# PCB-TLY-JACK-LEDPHOENIX.net
KiCad netlist of a schematic drawn in EAGLE
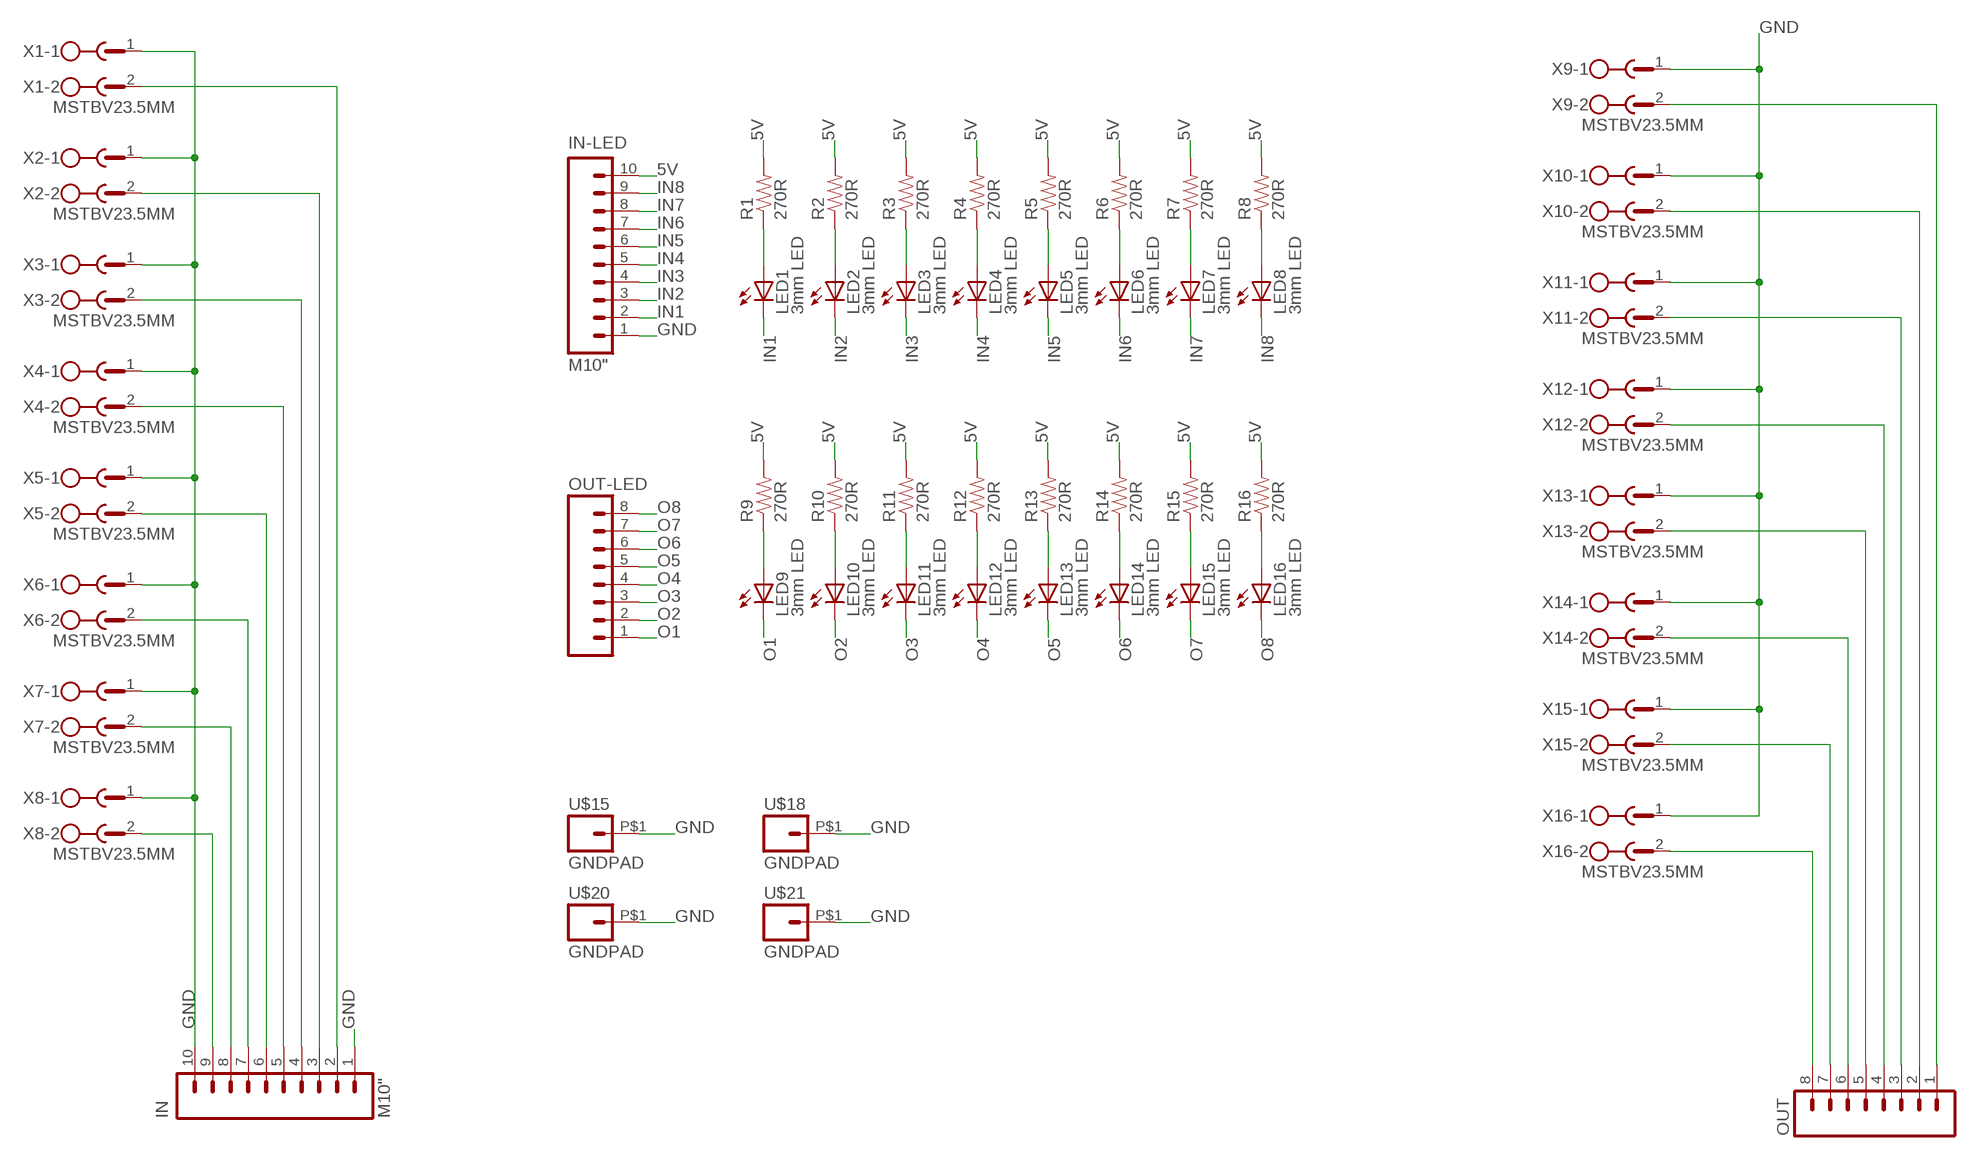
[diagram p0: schematic, sheet 1]

(export (version "E")
  (design (tool "Eeschema 10.0.6"))
  (components
    (comp (ref "IN")
      (value "M10\"")
      (footprint "eagle-import:1X10")
      (libsource (lib "eagle-import") (part "M10{dblquote}"))
    )
    (comp (ref "IN-LED")
      (value "M10\"")
      (footprint "eagle-import:1X10")
      (libsource (lib "eagle-import") (part "M10{dblquote}"))
    )
    (comp (ref "LED1")
      (value "3mm LED")
      (footprint "eagle-import:LED-1206")
      (libsource (lib "eagle-import") (part "LED1206"))
    )
    (comp (ref "LED2")
      (value "3mm LED")
      (footprint "eagle-import:LED-1206")
      (libsource (lib "eagle-import") (part "LED1206"))
    )
    (comp (ref "LED3")
      (value "3mm LED")
      (footprint "eagle-import:LED-1206")
      (libsource (lib "eagle-import") (part "LED1206"))
    )
    (comp (ref "LED4")
      (value "3mm LED")
      (footprint "eagle-import:LED-1206")
      (libsource (lib "eagle-import") (part "LED1206"))
    )
    (comp (ref "LED5")
      (value "3mm LED")
      (footprint "eagle-import:LED-1206")
      (libsource (lib "eagle-import") (part "LED1206"))
    )
    (comp (ref "LED6")
      (value "3mm LED")
      (footprint "eagle-import:LED-1206")
      (libsource (lib "eagle-import") (part "LED1206"))
    )
    (comp (ref "LED7")
      (value "3mm LED")
      (footprint "eagle-import:LED-1206")
      (libsource (lib "eagle-import") (part "LED1206"))
    )
    (comp (ref "LED8")
      (value "3mm LED")
      (footprint "eagle-import:LED-1206")
      (libsource (lib "eagle-import") (part "LED1206"))
    )
    (comp (ref "LED9")
      (value "3mm LED")
      (footprint "eagle-import:LED-1206")
      (libsource (lib "eagle-import") (part "LED1206"))
    )
    (comp (ref "LED10")
      (value "3mm LED")
      (footprint "eagle-import:LED-1206")
      (libsource (lib "eagle-import") (part "LED1206"))
    )
    (comp (ref "LED11")
      (value "3mm LED")
      (footprint "eagle-import:LED-1206")
      (libsource (lib "eagle-import") (part "LED1206"))
    )
    (comp (ref "LED12")
      (value "3mm LED")
      (footprint "eagle-import:LED-1206")
      (libsource (lib "eagle-import") (part "LED1206"))
    )
    (comp (ref "LED13")
      (value "3mm LED")
      (footprint "eagle-import:LED-1206")
      (libsource (lib "eagle-import") (part "LED1206"))
    )
    (comp (ref "LED14")
      (value "3mm LED")
      (footprint "eagle-import:LED-1206")
      (libsource (lib "eagle-import") (part "LED1206"))
    )
    (comp (ref "LED15")
      (value "3mm LED")
      (footprint "eagle-import:LED-1206")
      (libsource (lib "eagle-import") (part "LED1206"))
    )
    (comp (ref "LED16")
      (value "3mm LED")
      (footprint "eagle-import:LED-1206")
      (libsource (lib "eagle-import") (part "LED1206"))
    )
    (comp (ref "OUT")
      (value "M081X08")
      (footprint "eagle-import:1X08")
      (libsource (lib "eagle-import") (part "M081X08"))
    )
    (comp (ref "OUT-LED")
      (value "M081X08")
      (footprint "eagle-import:1X08")
      (libsource (lib "eagle-import") (part "M081X08"))
    )
    (comp (ref "R1")
      (value "270R")
      (footprint "eagle-import:0603-RES")
      (libsource (lib "eagle-import") (part "RESISTOR0603-RES"))
    )
    (comp (ref "R2")
      (value "270R")
      (footprint "eagle-import:0603-RES")
      (libsource (lib "eagle-import") (part "RESISTOR0603-RES"))
    )
    (comp (ref "R3")
      (value "270R")
      (footprint "eagle-import:0603-RES")
      (libsource (lib "eagle-import") (part "RESISTOR0603-RES"))
    )
    (comp (ref "R4")
      (value "270R")
      (footprint "eagle-import:0603-RES")
      (libsource (lib "eagle-import") (part "RESISTOR0603-RES"))
    )
    (comp (ref "R5")
      (value "270R")
      (footprint "eagle-import:0603-RES")
      (libsource (lib "eagle-import") (part "RESISTOR0603-RES"))
    )
    (comp (ref "R6")
      (value "270R")
      (footprint "eagle-import:0603-RES")
      (libsource (lib "eagle-import") (part "RESISTOR0603-RES"))
    )
    (comp (ref "R7")
      (value "270R")
      (footprint "eagle-import:0603-RES")
      (libsource (lib "eagle-import") (part "RESISTOR0603-RES"))
    )
    (comp (ref "R8")
      (value "270R")
      (footprint "eagle-import:0603-RES")
      (libsource (lib "eagle-import") (part "RESISTOR0603-RES"))
    )
    (comp (ref "R9")
      (value "270R")
      (footprint "eagle-import:0603-RES")
      (libsource (lib "eagle-import") (part "RESISTOR0603-RES"))
    )
    (comp (ref "R10")
      (value "270R")
      (footprint "eagle-import:0603-RES")
      (libsource (lib "eagle-import") (part "RESISTOR0603-RES"))
    )
    (comp (ref "R11")
      (value "270R")
      (footprint "eagle-import:0603-RES")
      (libsource (lib "eagle-import") (part "RESISTOR0603-RES"))
    )
    (comp (ref "R12")
      (value "270R")
      (footprint "eagle-import:0603-RES")
      (libsource (lib "eagle-import") (part "RESISTOR0603-RES"))
    )
    (comp (ref "R13")
      (value "270R")
      (footprint "eagle-import:0603-RES")
      (libsource (lib "eagle-import") (part "RESISTOR0603-RES"))
    )
    (comp (ref "R14")
      (value "270R")
      (footprint "eagle-import:0603-RES")
      (libsource (lib "eagle-import") (part "RESISTOR0603-RES"))
    )
    (comp (ref "R15")
      (value "270R")
      (footprint "eagle-import:0603-RES")
      (libsource (lib "eagle-import") (part "RESISTOR0603-RES"))
    )
    (comp (ref "R16")
      (value "270R")
      (footprint "eagle-import:0603-RES")
      (libsource (lib "eagle-import") (part "RESISTOR0603-RES"))
    )
    (comp (ref "U$15")
      (value "GNDPAD")
      (footprint "eagle-import:3.2MMPAD")
      (libsource (lib "eagle-import") (part "GNDPAD"))
    )
    (comp (ref "U$18")
      (value "GNDPAD")
      (footprint "eagle-import:3.2MMPAD")
      (libsource (lib "eagle-import") (part "GNDPAD"))
    )
    (comp (ref "U$20")
      (value "GNDPAD")
      (footprint "eagle-import:3.2MMPAD")
      (libsource (lib "eagle-import") (part "GNDPAD"))
    )
    (comp (ref "U$21")
      (value "GNDPAD")
      (footprint "eagle-import:3.2MMPAD")
      (libsource (lib "eagle-import") (part "GNDPAD"))
    )
    (comp (ref "X1")
      (value "MSTBV23.5MM")
      (footprint "eagle-import:MSTBV2-3.5")
      (libsource (lib "eagle-import") (part "MSTBV23.5MM"))
    )
    (comp (ref "X2")
      (value "MSTBV23.5MM")
      (footprint "eagle-import:MSTBV2-3.5")
      (libsource (lib "eagle-import") (part "MSTBV23.5MM"))
    )
    (comp (ref "X3")
      (value "MSTBV23.5MM")
      (footprint "eagle-import:MSTBV2-3.5")
      (libsource (lib "eagle-import") (part "MSTBV23.5MM"))
    )
    (comp (ref "X4")
      (value "MSTBV23.5MM")
      (footprint "eagle-import:MSTBV2-3.5")
      (libsource (lib "eagle-import") (part "MSTBV23.5MM"))
    )
    (comp (ref "X5")
      (value "MSTBV23.5MM")
      (footprint "eagle-import:MSTBV2-3.5")
      (libsource (lib "eagle-import") (part "MSTBV23.5MM"))
    )
    (comp (ref "X6")
      (value "MSTBV23.5MM")
      (footprint "eagle-import:MSTBV2-3.5")
      (libsource (lib "eagle-import") (part "MSTBV23.5MM"))
    )
    (comp (ref "X7")
      (value "MSTBV23.5MM")
      (footprint "eagle-import:MSTBV2-3.5")
      (libsource (lib "eagle-import") (part "MSTBV23.5MM"))
    )
    (comp (ref "X8")
      (value "MSTBV23.5MM")
      (footprint "eagle-import:MSTBV2-3.5")
      (libsource (lib "eagle-import") (part "MSTBV23.5MM"))
    )
    (comp (ref "X9")
      (value "MSTBV23.5MM")
      (footprint "eagle-import:MSTBV2-3.5")
      (libsource (lib "eagle-import") (part "MSTBV23.5MM"))
    )
    (comp (ref "X10")
      (value "MSTBV23.5MM")
      (footprint "eagle-import:MSTBV2-3.5")
      (libsource (lib "eagle-import") (part "MSTBV23.5MM"))
    )
    (comp (ref "X11")
      (value "MSTBV23.5MM")
      (footprint "eagle-import:MSTBV2-3.5")
      (libsource (lib "eagle-import") (part "MSTBV23.5MM"))
    )
    (comp (ref "X12")
      (value "MSTBV23.5MM")
      (footprint "eagle-import:MSTBV2-3.5")
      (libsource (lib "eagle-import") (part "MSTBV23.5MM"))
    )
    (comp (ref "X13")
      (value "MSTBV23.5MM")
      (footprint "eagle-import:MSTBV2-3.5")
      (libsource (lib "eagle-import") (part "MSTBV23.5MM"))
    )
    (comp (ref "X14")
      (value "MSTBV23.5MM")
      (footprint "eagle-import:MSTBV2-3.5")
      (libsource (lib "eagle-import") (part "MSTBV23.5MM"))
    )
    (comp (ref "X15")
      (value "MSTBV23.5MM")
      (footprint "eagle-import:MSTBV2-3.5")
      (libsource (lib "eagle-import") (part "MSTBV23.5MM"))
    )
    (comp (ref "X16")
      (value "MSTBV23.5MM")
      (footprint "eagle-import:MSTBV2-3.5")
      (libsource (lib "eagle-import") (part "MSTBV23.5MM"))
    )
  )
  (nets
    (net (code "1") (name "/5V") (class "Default")
      (node (ref "IN-LED") (pin "10") (pinfunction "10_10") (pintype "passive"))
      (node (ref "R1") (pin "2") (pinfunction "2_2") (pintype "passive"))
      (node (ref "R10") (pin "2") (pinfunction "2_2") (pintype "passive"))
      (node (ref "R11") (pin "2") (pinfunction "2_2") (pintype "passive"))
      (node (ref "R12") (pin "2") (pinfunction "2_2") (pintype "passive"))
      (node (ref "R13") (pin "2") (pinfunction "2_2") (pintype "passive"))
      (node (ref "R14") (pin "2") (pinfunction "2_2") (pintype "passive"))
      (node (ref "R15") (pin "2") (pinfunction "2_2") (pintype "passive"))
      (node (ref "R16") (pin "2") (pinfunction "2_2") (pintype "passive"))
      (node (ref "R2") (pin "2") (pinfunction "2_2") (pintype "passive"))
      (node (ref "R3") (pin "2") (pinfunction "2_2") (pintype "passive"))
      (node (ref "R4") (pin "2") (pinfunction "2_2") (pintype "passive"))
      (node (ref "R5") (pin "2") (pinfunction "2_2") (pintype "passive"))
      (node (ref "R6") (pin "2") (pinfunction "2_2") (pintype "passive"))
      (node (ref "R7") (pin "2") (pinfunction "2_2") (pintype "passive"))
      (node (ref "R8") (pin "2") (pinfunction "2_2") (pintype "passive"))
      (node (ref "R9") (pin "2") (pinfunction "2_2") (pintype "passive"))
    )
    (net (code "2") (name "/GND") (class "Default")
      (node (ref "IN") (pin "1") (pinfunction "1_1") (pintype "passive"))
      (node (ref "IN") (pin "10") (pinfunction "10_10") (pintype "passive"))
      (node (ref "IN-LED") (pin "1") (pinfunction "1_1") (pintype "passive"))
      (node (ref "U$15") (pin "P$1") (pinfunction "1_P$1") (pintype "passive"))
      (node (ref "U$18") (pin "P$1") (pinfunction "1_P$1") (pintype "passive"))
      (node (ref "U$20") (pin "P$1") (pinfunction "1_P$1") (pintype "passive"))
      (node (ref "U$21") (pin "P$1") (pinfunction "1_P$1") (pintype "passive"))
      (node (ref "X1") (pin "1") (pinfunction "1_1") (pintype "passive"))
      (node (ref "X10") (pin "1") (pinfunction "1_1") (pintype "passive"))
      (node (ref "X11") (pin "1") (pinfunction "1_1") (pintype "passive"))
      (node (ref "X12") (pin "1") (pinfunction "1_1") (pintype "passive"))
      (node (ref "X13") (pin "1") (pinfunction "1_1") (pintype "passive"))
      (node (ref "X14") (pin "1") (pinfunction "1_1") (pintype "passive"))
      (node (ref "X15") (pin "1") (pinfunction "1_1") (pintype "passive"))
      (node (ref "X16") (pin "1") (pinfunction "1_1") (pintype "passive"))
      (node (ref "X2") (pin "1") (pinfunction "1_1") (pintype "passive"))
      (node (ref "X3") (pin "1") (pinfunction "1_1") (pintype "passive"))
      (node (ref "X4") (pin "1") (pinfunction "1_1") (pintype "passive"))
      (node (ref "X5") (pin "1") (pinfunction "1_1") (pintype "passive"))
      (node (ref "X6") (pin "1") (pinfunction "1_1") (pintype "passive"))
      (node (ref "X7") (pin "1") (pinfunction "1_1") (pintype "passive"))
      (node (ref "X8") (pin "1") (pinfunction "1_1") (pintype "passive"))
      (node (ref "X9") (pin "1") (pinfunction "1_1") (pintype "passive"))
    )
    (net (code "3") (name "/IN1") (class "Default")
      (node (ref "IN-LED") (pin "2") (pinfunction "2_2") (pintype "passive"))
      (node (ref "LED1") (pin "C") (pinfunction "C_C") (pintype "passive"))
    )
    (net (code "4") (name "/IN2") (class "Default")
      (node (ref "IN-LED") (pin "3") (pinfunction "3_3") (pintype "passive"))
      (node (ref "LED2") (pin "C") (pinfunction "C_C") (pintype "passive"))
    )
    (net (code "5") (name "/IN3") (class "Default")
      (node (ref "IN-LED") (pin "4") (pinfunction "4_4") (pintype "passive"))
      (node (ref "LED3") (pin "C") (pinfunction "C_C") (pintype "passive"))
    )
    (net (code "6") (name "/IN4") (class "Default")
      (node (ref "IN-LED") (pin "5") (pinfunction "5_5") (pintype "passive"))
      (node (ref "LED4") (pin "C") (pinfunction "C_C") (pintype "passive"))
    )
    (net (code "7") (name "/IN5") (class "Default")
      (node (ref "IN-LED") (pin "6") (pinfunction "6_6") (pintype "passive"))
      (node (ref "LED5") (pin "C") (pinfunction "C_C") (pintype "passive"))
    )
    (net (code "8") (name "/IN6") (class "Default")
      (node (ref "IN-LED") (pin "7") (pinfunction "7_7") (pintype "passive"))
      (node (ref "LED6") (pin "C") (pinfunction "C_C") (pintype "passive"))
    )
    (net (code "9") (name "/IN7") (class "Default")
      (node (ref "IN-LED") (pin "8") (pinfunction "8_8") (pintype "passive"))
      (node (ref "LED7") (pin "C") (pinfunction "C_C") (pintype "passive"))
    )
    (net (code "10") (name "/IN8") (class "Default")
      (node (ref "IN-LED") (pin "9") (pinfunction "9_9") (pintype "passive"))
      (node (ref "LED8") (pin "C") (pinfunction "C_C") (pintype "passive"))
    )
    (net (code "11") (name "/O1") (class "Default")
      (node (ref "LED9") (pin "C") (pinfunction "C_C") (pintype "passive"))
      (node (ref "OUT-LED") (pin "1") (pinfunction "1_1") (pintype "passive"))
    )
    (net (code "12") (name "/O2") (class "Default")
      (node (ref "LED10") (pin "C") (pinfunction "C_C") (pintype "passive"))
      (node (ref "OUT-LED") (pin "2") (pinfunction "2_2") (pintype "passive"))
    )
    (net (code "13") (name "/O3") (class "Default")
      (node (ref "LED11") (pin "C") (pinfunction "C_C") (pintype "passive"))
      (node (ref "OUT-LED") (pin "3") (pinfunction "3_3") (pintype "passive"))
    )
    (net (code "14") (name "/O4") (class "Default")
      (node (ref "LED12") (pin "C") (pinfunction "C_C") (pintype "passive"))
      (node (ref "OUT-LED") (pin "4") (pinfunction "4_4") (pintype "passive"))
    )
    (net (code "15") (name "/O5") (class "Default")
      (node (ref "LED13") (pin "C") (pinfunction "C_C") (pintype "passive"))
      (node (ref "OUT-LED") (pin "5") (pinfunction "5_5") (pintype "passive"))
    )
    (net (code "16") (name "/O6") (class "Default")
      (node (ref "LED14") (pin "C") (pinfunction "C_C") (pintype "passive"))
      (node (ref "OUT-LED") (pin "6") (pinfunction "6_6") (pintype "passive"))
    )
    (net (code "17") (name "/O7") (class "Default")
      (node (ref "LED15") (pin "C") (pinfunction "C_C") (pintype "passive"))
      (node (ref "OUT-LED") (pin "7") (pinfunction "7_7") (pintype "passive"))
    )
    (net (code "18") (name "/O8") (class "Default")
      (node (ref "LED16") (pin "C") (pinfunction "C_C") (pintype "passive"))
      (node (ref "OUT-LED") (pin "8") (pinfunction "8_8") (pintype "passive"))
    )
    (net (code "19") (name "Net-(LED1-PadA)") (class "Default")
      (node (ref "LED1") (pin "A") (pinfunction "A_A") (pintype "passive"))
      (node (ref "R1") (pin "1") (pinfunction "1_1") (pintype "passive"))
    )
    (net (code "20") (name "Net-(LED2-PadA)") (class "Default")
      (node (ref "LED2") (pin "A") (pinfunction "A_A") (pintype "passive"))
      (node (ref "R2") (pin "1") (pinfunction "1_1") (pintype "passive"))
    )
    (net (code "21") (name "Net-(LED3-PadA)") (class "Default")
      (node (ref "LED3") (pin "A") (pinfunction "A_A") (pintype "passive"))
      (node (ref "R3") (pin "1") (pinfunction "1_1") (pintype "passive"))
    )
    (net (code "22") (name "Net-(LED4-PadA)") (class "Default")
      (node (ref "LED4") (pin "A") (pinfunction "A_A") (pintype "passive"))
      (node (ref "R4") (pin "1") (pinfunction "1_1") (pintype "passive"))
    )
    (net (code "23") (name "Net-(LED5-PadA)") (class "Default")
      (node (ref "LED5") (pin "A") (pinfunction "A_A") (pintype "passive"))
      (node (ref "R5") (pin "1") (pinfunction "1_1") (pintype "passive"))
    )
    (net (code "24") (name "Net-(LED6-PadA)") (class "Default")
      (node (ref "LED6") (pin "A") (pinfunction "A_A") (pintype "passive"))
      (node (ref "R6") (pin "1") (pinfunction "1_1") (pintype "passive"))
    )
    (net (code "25") (name "Net-(LED7-PadA)") (class "Default")
      (node (ref "LED7") (pin "A") (pinfunction "A_A") (pintype "passive"))
      (node (ref "R7") (pin "1") (pinfunction "1_1") (pintype "passive"))
    )
    (net (code "26") (name "Net-(LED8-PadA)") (class "Default")
      (node (ref "LED8") (pin "A") (pinfunction "A_A") (pintype "passive"))
      (node (ref "R8") (pin "1") (pinfunction "1_1") (pintype "passive"))
    )
    (net (code "27") (name "Net-(LED9-PadA)") (class "Default")
      (node (ref "LED9") (pin "A") (pinfunction "A_A") (pintype "passive"))
      (node (ref "R9") (pin "1") (pinfunction "1_1") (pintype "passive"))
    )
    (net (code "28") (name "Net-(LED10-PadA)") (class "Default")
      (node (ref "LED10") (pin "A") (pinfunction "A_A") (pintype "passive"))
      (node (ref "R10") (pin "1") (pinfunction "1_1") (pintype "passive"))
    )
    (net (code "29") (name "Net-(LED11-PadA)") (class "Default")
      (node (ref "LED11") (pin "A") (pinfunction "A_A") (pintype "passive"))
      (node (ref "R11") (pin "1") (pinfunction "1_1") (pintype "passive"))
    )
    (net (code "30") (name "Net-(LED12-PadA)") (class "Default")
      (node (ref "LED12") (pin "A") (pinfunction "A_A") (pintype "passive"))
      (node (ref "R12") (pin "1") (pinfunction "1_1") (pintype "passive"))
    )
    (net (code "31") (name "Net-(LED13-PadA)") (class "Default")
      (node (ref "LED13") (pin "A") (pinfunction "A_A") (pintype "passive"))
      (node (ref "R13") (pin "1") (pinfunction "1_1") (pintype "passive"))
    )
    (net (code "32") (name "Net-(LED14-PadA)") (class "Default")
      (node (ref "LED14") (pin "A") (pinfunction "A_A") (pintype "passive"))
      (node (ref "R14") (pin "1") (pinfunction "1_1") (pintype "passive"))
    )
    (net (code "33") (name "Net-(LED15-PadA)") (class "Default")
      (node (ref "LED15") (pin "A") (pinfunction "A_A") (pintype "passive"))
      (node (ref "R15") (pin "1") (pinfunction "1_1") (pintype "passive"))
    )
    (net (code "34") (name "Net-(LED16-PadA)") (class "Default")
      (node (ref "LED16") (pin "A") (pinfunction "A_A") (pintype "passive"))
      (node (ref "R16") (pin "1") (pinfunction "1_1") (pintype "passive"))
    )
    (net (code "35") (name "Net-(X1B-1)") (class "Default")
      (node (ref "IN") (pin "2") (pinfunction "2_2") (pintype "passive"))
      (node (ref "X1") (pin "2") (pinfunction "1_2") (pintype "passive"))
    )
    (net (code "36") (name "Net-(X2B-1)") (class "Default")
      (node (ref "IN") (pin "3") (pinfunction "3_3") (pintype "passive"))
      (node (ref "X2") (pin "2") (pinfunction "1_2") (pintype "passive"))
    )
    (net (code "37") (name "Net-(X3B-1)") (class "Default")
      (node (ref "IN") (pin "4") (pinfunction "4_4") (pintype "passive"))
      (node (ref "X3") (pin "2") (pinfunction "1_2") (pintype "passive"))
    )
    (net (code "38") (name "Net-(X4B-1)") (class "Default")
      (node (ref "IN") (pin "5") (pinfunction "5_5") (pintype "passive"))
      (node (ref "X4") (pin "2") (pinfunction "1_2") (pintype "passive"))
    )
    (net (code "39") (name "Net-(X5B-1)") (class "Default")
      (node (ref "IN") (pin "6") (pinfunction "6_6") (pintype "passive"))
      (node (ref "X5") (pin "2") (pinfunction "1_2") (pintype "passive"))
    )
    (net (code "40") (name "Net-(X6B-1)") (class "Default")
      (node (ref "IN") (pin "7") (pinfunction "7_7") (pintype "passive"))
      (node (ref "X6") (pin "2") (pinfunction "1_2") (pintype "passive"))
    )
    (net (code "41") (name "Net-(X7B-1)") (class "Default")
      (node (ref "IN") (pin "8") (pinfunction "8_8") (pintype "passive"))
      (node (ref "X7") (pin "2") (pinfunction "1_2") (pintype "passive"))
    )
    (net (code "42") (name "Net-(X8B-1)") (class "Default")
      (node (ref "IN") (pin "9") (pinfunction "9_9") (pintype "passive"))
      (node (ref "X8") (pin "2") (pinfunction "1_2") (pintype "passive"))
    )
    (net (code "43") (name "Net-(X9B-1)") (class "Default")
      (node (ref "OUT") (pin "1") (pinfunction "1_1") (pintype "passive"))
      (node (ref "X9") (pin "2") (pinfunction "1_2") (pintype "passive"))
    )
    (net (code "44") (name "Net-(X10B-1)") (class "Default")
      (node (ref "OUT") (pin "2") (pinfunction "2_2") (pintype "passive"))
      (node (ref "X10") (pin "2") (pinfunction "1_2") (pintype "passive"))
    )
    (net (code "45") (name "Net-(X11B-1)") (class "Default")
      (node (ref "OUT") (pin "3") (pinfunction "3_3") (pintype "passive"))
      (node (ref "X11") (pin "2") (pinfunction "1_2") (pintype "passive"))
    )
    (net (code "46") (name "Net-(X12B-1)") (class "Default")
      (node (ref "OUT") (pin "4") (pinfunction "4_4") (pintype "passive"))
      (node (ref "X12") (pin "2") (pinfunction "1_2") (pintype "passive"))
    )
    (net (code "47") (name "Net-(X13B-1)") (class "Default")
      (node (ref "OUT") (pin "5") (pinfunction "5_5") (pintype "passive"))
      (node (ref "X13") (pin "2") (pinfunction "1_2") (pintype "passive"))
    )
    (net (code "48") (name "Net-(X14B-1)") (class "Default")
      (node (ref "OUT") (pin "6") (pinfunction "6_6") (pintype "passive"))
      (node (ref "X14") (pin "2") (pinfunction "1_2") (pintype "passive"))
    )
    (net (code "49") (name "Net-(X15B-1)") (class "Default")
      (node (ref "OUT") (pin "7") (pinfunction "7_7") (pintype "passive"))
      (node (ref "X15") (pin "2") (pinfunction "1_2") (pintype "passive"))
    )
    (net (code "50") (name "Net-(X16B-1)") (class "Default")
      (node (ref "OUT") (pin "8") (pinfunction "8_8") (pintype "passive"))
      (node (ref "X16") (pin "2") (pinfunction "1_2") (pintype "passive"))
    )
  )
)
